# main.net
KiCad netlist of a schematic drawn in Altium Designer
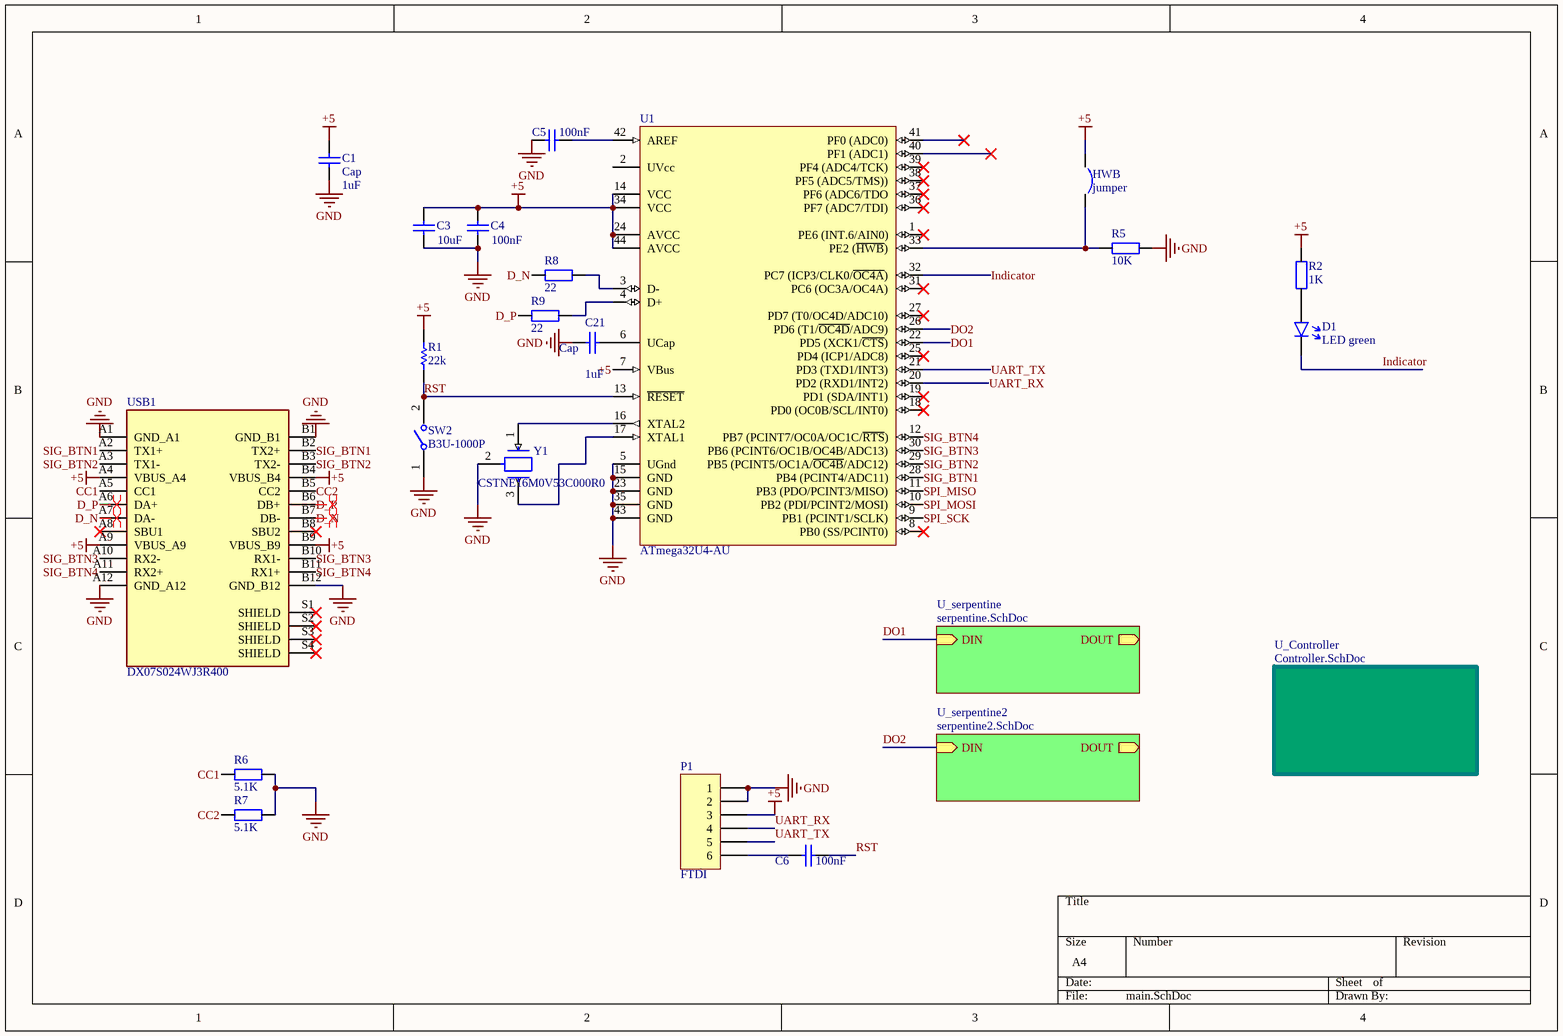
[diagram p0: main.SchDoc]

(export (version "E")
  (design (tool "Eeschema 10.0.6"))
  (components
    (comp (ref "C1")
      (value "Cap")
      (footprint "6-0805_M")
      (description "C107456")
      (fields (field (name "ALTIUM_VALUE") "1uF") (field (name "PUBLISHER") "Altium Limited"))
      (libsource (lib "Miscellaneous Devices") (part "Cap"))
    )
    (comp (ref "C3")
      (value "10uF")
      (footprint "6-0805_N")
      (description "C40894")
      (fields (field (name "Comment") "Cap") (field (name "PUBLISHER") "Altium Limited"))
      (libsource (lib "Miscellaneous Devices") (part "Cap"))
    )
    (comp (ref "C4")
      (value "100nF")
      (footprint "6-0805_N")
      (description "C282730")
      (fields (field (name "Comment") "Cap") (field (name "PUBLISHER") "Altium Limited"))
      (libsource (lib "Miscellaneous Devices") (part "Cap"))
    )
    (comp (ref "C5")
      (value "100nF")
      (footprint "6-0805_N")
      (description "C282730")
      (fields (field (name "Comment") "Cap") (field (name "PUBLISHER") "Altium Limited"))
      (libsource (lib "Miscellaneous Devices") (part "Cap"))
    )
    (comp (ref "C6")
      (value "100nF")
      (footprint "6-0805_N")
      (description "C282730")
      (fields (field (name "Comment") "Cap") (field (name "PUBLISHER") "Altium Limited"))
      (libsource (lib "Miscellaneous Devices") (part "Cap"))
    )
    (comp (ref "C21")
      (value "Cap")
      (footprint "6-0805_N")
      (description "C393688")
      (fields (field (name "ALTIUM_VALUE") "1uF") (field (name "PUBLISHER") "Altium Limited"))
      (libsource (lib "Miscellaneous Devices") (part "Cap"))
    )
    (comp (ref "D1")
      (value "LED green")
      (footprint "LED0805")
      (description "C84260")
      (libsource (lib "rgbleds") (part "LED single"))
    )
    (comp (ref "HWB")
      (value "jumper")
      (footprint "smd jumper")
      (libsource (lib "Brillz4Components") (part "jumper"))
    )
    (comp (ref "P1")
      (value "FTDI")
      (footprint "HDR1X6H")
      (description "Header, 6-Pin, Right Angle")
      (fields (field (name "PUBLISHER") "Altium Limited"))
      (libsource (lib "Miscellaneous Connectors") (part "Header 6H"))
    )
    (comp (ref "R1")
      (value "22k")
      (footprint "6-0805_N")
      (description "C269535")
      (fields (field (name "PUBLISHER") "Altium Limited"))
      (libsource (lib "Miscellaneous Devices") (part "Res1"))
    )
    (comp (ref "R2")
      (value "1K")
      (footprint "RES0805")
      (description "C269744")
      (libsource (lib "blandat") (part "Resistor"))
    )
    (comp (ref "R5")
      (value "10K")
      (footprint "RES0805")
      (description "C269744")
      (libsource (lib "blandat") (part "Resistor"))
    )
    (comp (ref "R6")
      (value "5.1K")
      (footprint "RES0805")
      (description "C269744")
      (libsource (lib "blandat") (part "Resistor"))
    )
    (comp (ref "R7")
      (value "5.1K")
      (footprint "RES0805")
      (description "C269744")
      (libsource (lib "blandat") (part "Resistor"))
    )
    (comp (ref "R8")
      (value "22")
      (footprint "RES0805")
      (description "C269744")
      (libsource (lib "blandat") (part "Resistor"))
    )
    (comp (ref "R9")
      (value "22")
      (footprint "RES0805")
      (description "C269744")
      (libsource (lib "blandat") (part "Resistor"))
    )
    (comp (ref "SW2")
      (value "B3U-1000P")
      (footprint "FP-B3U-1000P-MFG")
      (description "SWITCH TACTILE SPST-NO 0.05A 12V")
      (libsource (lib "Altium Content Vault") (part "ae622034201233ca1abcedc05908f33"))
    )
    (comp (ref "U1")
      (value "ATmega32U4-AU")
      (footprint "44ML_M")
      (libsource (lib "Altium Content Vault") (part "MC-8B-ATM16U4-SQ44"))
    )
    (comp (ref "USB1")
      (value "DX07S024WJ3R400")
      (footprint "JAE_DX07S024WJ3R400")
      (description "Conn Rcpt Usb3.1 Typec Smd Vert")
      (fields (field (name "MF") "{'manufacturer': u'JAE Electronics'}"))
      (libsource (lib "*") (part "DX07S024WJ3R400"))
    )
    (comp (ref "Y1")
      (value "CSTNE16M0V53C000R0")
      (footprint "FP-CSTNE16M0V53C000R0-MFG")
      (description "CERAMIC RES 16.0000MHZ 15PF SMD")
      (libsource (lib "Altium Content Vault") (part "7d37667f5012bb31280c8009ddd0b1c"))
    )
  )
  (nets
    (net (code "1") (name "+5") (class "Default")
      (node (ref "C1") (pin "1") (pinfunction "1_1") (pintype "passive"))
      (node (ref "C3") (pin "1") (pinfunction "1_1") (pintype "passive"))
      (node (ref "C4") (pin "1") (pinfunction "1_1") (pintype "passive"))
      (node (ref "HWB") (pin "1") (pinfunction "1_1") (pintype "passive"))
      (node (ref "P1") (pin "3") (pinfunction "3_3") (pintype "passive"))
      (node (ref "R1") (pin "2") (pinfunction "2_2") (pintype "passive"))
      (node (ref "R2") (pin "1") (pinfunction "1_1") (pintype "passive"))
      (node (ref "U1") (pin "14") (pinfunction "VCC_14") (pintype "power_in"))
      (node (ref "U1") (pin "24") (pinfunction "AVCC_24") (pintype "power_in"))
      (node (ref "U1") (pin "34") (pinfunction "VCC_34") (pintype "power_in"))
      (node (ref "U1") (pin "44") (pinfunction "AVCC_44") (pintype "power_in"))
      (node (ref "U1") (pin "7") (pinfunction "VBus_7") (pintype "input"))
      (node (ref "USB1") (pin "A4") (pinfunction "VBUS_A4_A4") (pintype "passive"))
      (node (ref "USB1") (pin "A9") (pinfunction "VBUS_A9_A9") (pintype "passive"))
      (node (ref "USB1") (pin "B4") (pinfunction "VBUS_B4_B4") (pintype "passive"))
      (node (ref "USB1") (pin "B9") (pinfunction "VBUS_B9_B9") (pintype "passive"))
    )
    (net (code "2") (name "/CC1") (class "Default")
      (node (ref "R6") (pin "1") (pinfunction "1_1") (pintype "passive"))
      (node (ref "USB1") (pin "A5") (pinfunction "CC1_A5") (pintype "passive"))
    )
    (net (code "3") (name "/CC2") (class "Default")
      (node (ref "R7") (pin "1") (pinfunction "1_1") (pintype "passive"))
      (node (ref "USB1") (pin "B5") (pinfunction "CC2_B5") (pintype "passive"))
    )
    (net (code "4") (name "/DO1") (class "Default")
      (node (ref "U1") (pin "22") (pinfunction "PD5_(XCK1/~{CTS})_22") (pintype "bidirectional"))
    )
    (net (code "5") (name "/DO2") (class "Default")
      (node (ref "U1") (pin "26") (pinfunction "PD6_(T1/~{OC4D}/ADC9)_26") (pintype "bidirectional"))
    )
    (net (code "8") (name "/D_N") (class "Default")
      (node (ref "R8") (pin "1") (pinfunction "1_1") (pintype "passive"))
      (node (ref "USB1") (pin "A7") (pinfunction "DA-_A7") (pintype "passive"))
      (node (ref "USB1") (pin "B7") (pinfunction "DB-_B7") (pintype "passive"))
    )
    (net (code "9") (name "/D_P") (class "Default")
      (node (ref "R9") (pin "1") (pinfunction "1_1") (pintype "passive"))
      (node (ref "USB1") (pin "A6") (pinfunction "DA+_A6") (pintype "passive"))
      (node (ref "USB1") (pin "B6") (pinfunction "DB+_B6") (pintype "passive"))
    )
    (net (code "10") (name "/Indicator") (class "Default")
      (node (ref "D1") (pin "2") (pinfunction "2_2") (pintype "passive"))
      (node (ref "U1") (pin "32") (pinfunction "PC7_(ICP3/CLK0/~{OC4A})_32") (pintype "bidirectional"))
    )
    (net (code "11") (name "/RST") (class "Default")
      (node (ref "C6") (pin "1") (pinfunction "1_1") (pintype "passive"))
      (node (ref "R1") (pin "1") (pinfunction "1_1") (pintype "passive"))
      (node (ref "SW2") (pin "2") (pinfunction "2_2") (pintype "passive"))
      (node (ref "U1") (pin "13") (pinfunction "~{RESET}_13") (pintype "input"))
    )
    (net (code "12") (name "/SIG_BTN1") (class "Default")
      (node (ref "U1") (pin "28") (pinfunction "PB4_(PCINT4/ADC11)_28") (pintype "bidirectional"))
      (node (ref "USB1") (pin "A2") (pinfunction "TX1+_A2") (pintype "passive"))
      (node (ref "USB1") (pin "B2") (pinfunction "TX2+_B2") (pintype "passive"))
    )
    (net (code "13") (name "/SIG_BTN2") (class "Default")
      (node (ref "U1") (pin "29") (pinfunction "PB5_(PCINT5/OC1A/~{OC4B}/ADC12)_29") (pintype "bidirectional"))
      (node (ref "USB1") (pin "A3") (pinfunction "TX1-_A3") (pintype "passive"))
      (node (ref "USB1") (pin "B3") (pinfunction "TX2-_B3") (pintype "passive"))
    )
    (net (code "14") (name "/SIG_BTN3") (class "Default")
      (node (ref "U1") (pin "30") (pinfunction "PB6_(PCINT6/OC1B/OC4B/ADC13)_30") (pintype "bidirectional"))
      (node (ref "USB1") (pin "A10") (pinfunction "RX2-_A10") (pintype "passive"))
      (node (ref "USB1") (pin "B10") (pinfunction "RX1-_B10") (pintype "passive"))
    )
    (net (code "15") (name "/SIG_BTN4") (class "Default")
      (node (ref "U1") (pin "12") (pinfunction "PB7_(PCINT7/OC0A/OC1C/~{RTS})_12") (pintype "bidirectional"))
      (node (ref "USB1") (pin "A11") (pinfunction "RX2+_A11") (pintype "passive"))
      (node (ref "USB1") (pin "B11") (pinfunction "RX1+_B11") (pintype "passive"))
    )
    (net (code "16") (name "/SPI_MISO") (class "Default")
      (node (ref "U1") (pin "11") (pinfunction "PB3_(PDO/PCINT3/MISO)_11") (pintype "bidirectional"))
    )
    (net (code "17") (name "/SPI_MOSI") (class "Default")
      (node (ref "U1") (pin "10") (pinfunction "PB2_(PDI/PCINT2/MOSI)_10") (pintype "bidirectional"))
    )
    (net (code "18") (name "/SPI_SCK") (class "Default")
      (node (ref "U1") (pin "9") (pinfunction "PB1_(PCINT1/SCLK)_9") (pintype "bidirectional"))
    )
    (net (code "19") (name "/UART_RX") (class "Default")
      (node (ref "P1") (pin "4") (pinfunction "4_4") (pintype "passive"))
      (node (ref "U1") (pin "20") (pinfunction "PD2_(RXD1/INT2)_20") (pintype "bidirectional"))
    )
    (net (code "20") (name "/UART_TX") (class "Default")
      (node (ref "P1") (pin "5") (pinfunction "5_5") (pintype "passive"))
      (node (ref "U1") (pin "21") (pinfunction "PD3_(TXD1/INT3)_21") (pintype "bidirectional"))
    )
    (net (code "21") (name "GND") (class "Default")
      (node (ref "C1") (pin "2") (pinfunction "2_2") (pintype "passive"))
      (node (ref "C21") (pin "2") (pinfunction "2_2") (pintype "passive"))
      (node (ref "C3") (pin "2") (pinfunction "2_2") (pintype "passive"))
      (node (ref "C4") (pin "2") (pinfunction "2_2") (pintype "passive"))
      (node (ref "C5") (pin "2") (pinfunction "2_2") (pintype "passive"))
      (node (ref "P1") (pin "1") (pinfunction "1_1") (pintype "passive"))
      (node (ref "P1") (pin "2") (pinfunction "2_2") (pintype "passive"))
      (node (ref "R5") (pin "2") (pinfunction "2_2") (pintype "passive"))
      (node (ref "R6") (pin "2") (pinfunction "2_2") (pintype "passive"))
      (node (ref "R7") (pin "2") (pinfunction "2_2") (pintype "passive"))
      (node (ref "SW2") (pin "1") (pinfunction "1_1") (pintype "passive"))
      (node (ref "U1") (pin "15") (pinfunction "GND_15") (pintype "power_in"))
      (node (ref "U1") (pin "23") (pinfunction "GND_23") (pintype "power_in"))
      (node (ref "U1") (pin "35") (pinfunction "GND_35") (pintype "power_in"))
      (node (ref "U1") (pin "43") (pinfunction "GND_43") (pintype "power_in"))
      (node (ref "U1") (pin "5") (pinfunction "UGnd_5") (pintype "power_in"))
      (node (ref "USB1") (pin "A1") (pinfunction "GND_A1_A1") (pintype "passive"))
      (node (ref "USB1") (pin "A12") (pinfunction "GND_A12_A12") (pintype "passive"))
      (node (ref "USB1") (pin "B1") (pinfunction "GND_B1_B1") (pintype "passive"))
      (node (ref "USB1") (pin "B12") (pinfunction "GND_B12_B12") (pintype "passive"))
      (node (ref "Y1") (pin "2") (pinfunction "GND_2") (pintype "power_in"))
    )
    (net (code "22") (name "Net-(C6-Pad2)") (class "Default")
      (node (ref "C6") (pin "2") (pinfunction "2_2") (pintype "passive"))
      (node (ref "P1") (pin "6") (pinfunction "6_6") (pintype "passive"))
    )
    (net (code "23") (name "Net-(D1-A)") (class "Default")
      (node (ref "D1") (pin "1") (pinfunction "A_1") (pintype "passive"))
      (node (ref "R2") (pin "2") (pinfunction "2_2") (pintype "passive"))
    )
    (net (code "24") (name "Net-(U1-AREF)") (class "Default")
      (node (ref "C5") (pin "1") (pinfunction "1_1") (pintype "passive"))
      (node (ref "U1") (pin "42") (pinfunction "AREF_42") (pintype "input"))
    )
    (net (code "25") (name "Net-(U1-D+)") (class "Default")
      (node (ref "R9") (pin "2") (pinfunction "2_2") (pintype "passive"))
      (node (ref "U1") (pin "4") (pinfunction "D+_4") (pintype "bidirectional"))
    )
    (net (code "26") (name "Net-(U1-D-)") (class "Default")
      (node (ref "R8") (pin "2") (pinfunction "2_2") (pintype "passive"))
      (node (ref "U1") (pin "3") (pinfunction "D-_3") (pintype "bidirectional"))
    )
    (net (code "27") (name "Net-(U1-PE2_(~{HWB}))") (class "Default")
      (node (ref "HWB") (pin "2") (pinfunction "2_2") (pintype "passive"))
      (node (ref "R5") (pin "1") (pinfunction "1_1") (pintype "passive"))
      (node (ref "U1") (pin "33") (pinfunction "PE2_(~{HWB})_33") (pintype "bidirectional"))
    )
    (net (code "28") (name "Net-(U1-UCap)") (class "Default")
      (node (ref "C21") (pin "1") (pinfunction "1_1") (pintype "passive"))
      (node (ref "U1") (pin "6") (pinfunction "UCap_6") (pintype "passive"))
    )
    (net (code "29") (name "Net-(U1-XTAL1)") (class "Default")
      (node (ref "U1") (pin "17") (pinfunction "XTAL1_17") (pintype "input"))
      (node (ref "Y1") (pin "3") (pinfunction "Output_3") (pintype "output"))
    )
    (net (code "30") (name "Net-(U1-XTAL2)") (class "Default")
      (node (ref "U1") (pin "16") (pinfunction "XTAL2_16") (pintype "output"))
      (node (ref "Y1") (pin "1") (pinfunction "Input_1") (pintype "input"))
    )
    (net (code "31") (name "unconnected-(U1-PB0_(SS{slash}PCINT0)-Pad8)") (class "Default")
      (node (ref "U1") (pin "8") (pinfunction "PB0_(SS/PCINT0)_8") (pintype "bidirectional+no_connect"))
    )
    (net (code "32") (name "unconnected-(U1-PC6_(OC3A{slash}OC4A)-Pad31)") (class "Default")
      (node (ref "U1") (pin "31") (pinfunction "PC6_(OC3A/OC4A)_31") (pintype "bidirectional+no_connect"))
    )
    (net (code "33") (name "unconnected-(U1-PD0_(OC0B{slash}SCL{slash}INT0)-Pad18)") (class "Default")
      (node (ref "U1") (pin "18") (pinfunction "PD0_(OC0B/SCL/INT0)_18") (pintype "bidirectional+no_connect"))
    )
    (net (code "34") (name "unconnected-(U1-PD1_(SDA{slash}INT1)-Pad19)") (class "Default")
      (node (ref "U1") (pin "19") (pinfunction "PD1_(SDA/INT1)_19") (pintype "bidirectional+no_connect"))
    )
    (net (code "35") (name "unconnected-(U1-PD4_(ICP1{slash}ADC8)-Pad25)") (class "Default")
      (node (ref "U1") (pin "25") (pinfunction "PD4_(ICP1/ADC8)_25") (pintype "bidirectional+no_connect"))
    )
    (net (code "36") (name "unconnected-(U1-PD7_(T0{slash}OC4D{slash}ADC10)-Pad27)") (class "Default")
      (node (ref "U1") (pin "27") (pinfunction "PD7_(T0/OC4D/ADC10)_27") (pintype "bidirectional+no_connect"))
    )
    (net (code "37") (name "unconnected-(U1-PE6_(INT.6{slash}AIN0)-Pad1)") (class "Default")
      (node (ref "U1") (pin "1") (pinfunction "PE6_(INT.6/AIN0)_1") (pintype "bidirectional+no_connect"))
    )
    (net (code "38") (name "unconnected-(U1-PF0_(ADC0)-Pad41)") (class "Default")
      (node (ref "U1") (pin "41") (pinfunction "PF0_(ADC0)_41") (pintype "bidirectional+no_connect"))
    )
    (net (code "39") (name "unconnected-(U1-PF1_(ADC1)-Pad40)") (class "Default")
      (node (ref "U1") (pin "40") (pinfunction "PF1_(ADC1)_40") (pintype "bidirectional+no_connect"))
    )
    (net (code "40") (name "unconnected-(U1-PF4_(ADC4{slash}TCK)-Pad39)") (class "Default")
      (node (ref "U1") (pin "39") (pinfunction "PF4_(ADC4/TCK)_39") (pintype "bidirectional+no_connect"))
    )
    (net (code "41") (name "unconnected-(U1-PF5_(ADC5{slash}TMS))-Pad38)") (class "Default")
      (node (ref "U1") (pin "38") (pinfunction "PF5_(ADC5/TMS))_38") (pintype "bidirectional+no_connect"))
    )
    (net (code "42") (name "unconnected-(U1-PF6_(ADC6{slash}TDO-Pad37)") (class "Default")
      (node (ref "U1") (pin "37") (pinfunction "PF6_(ADC6/TDO_37") (pintype "bidirectional+no_connect"))
    )
    (net (code "43") (name "unconnected-(U1-PF7_(ADC7{slash}TDI)-Pad36)") (class "Default")
      (node (ref "U1") (pin "36") (pinfunction "PF7_(ADC7/TDI)_36") (pintype "bidirectional+no_connect"))
    )
    (net (code "44") (name "unconnected-(U1-UVcc-Pad2)") (class "Default")
      (node (ref "U1") (pin "2") (pinfunction "UVcc_2") (pintype "power_in"))
    )
    (net (code "45") (name "unconnected-(USB1-SBU1-PadA8)") (class "Default")
      (node (ref "USB1") (pin "A8") (pinfunction "SBU1_A8") (pintype "passive+no_connect"))
    )
    (net (code "46") (name "unconnected-(USB1-SBU2-PadB8)") (class "Default")
      (node (ref "USB1") (pin "B8") (pinfunction "SBU2_B8") (pintype "passive+no_connect"))
    )
    (net (code "47") (name "unconnected-(USB1-SHIELD-PadS1)") (class "Default")
      (node (ref "USB1") (pin "S1") (pinfunction "SHIELD_S1") (pintype "passive+no_connect"))
    )
    (net (code "48") (name "unconnected-(USB1-SHIELD-PadS2)") (class "Default")
      (node (ref "USB1") (pin "S2") (pinfunction "SHIELD_S2") (pintype "passive+no_connect"))
    )
    (net (code "49") (name "unconnected-(USB1-SHIELD-PadS3)") (class "Default")
      (node (ref "USB1") (pin "S3") (pinfunction "SHIELD_S3") (pintype "passive+no_connect"))
    )
    (net (code "50") (name "unconnected-(USB1-SHIELD-PadS4)") (class "Default")
      (node (ref "USB1") (pin "S4") (pinfunction "SHIELD_S4") (pintype "passive+no_connect"))
    )
  )
)
